# Main.net
KiCad netlist of a schematic drawn in Altium Designer
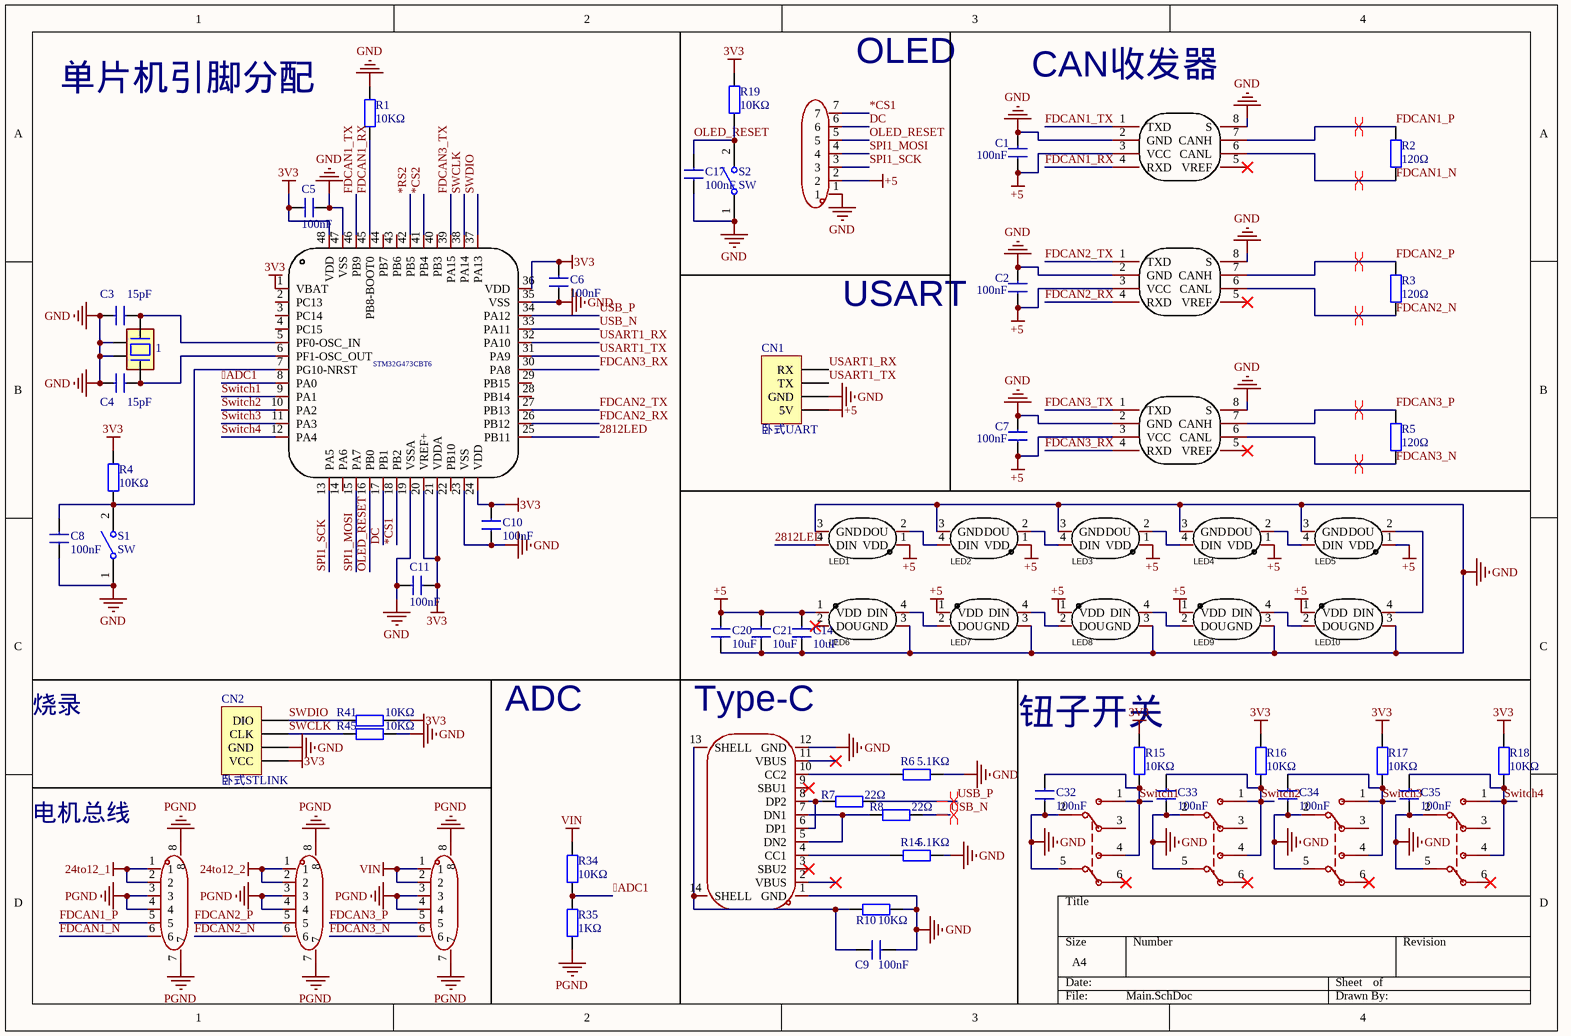
[diagram p0: Main.SchDoc]

(export (version "E")
  (design (tool "Eeschema 10.0.6"))
  (components
    (comp (ref "1")
      (value "3225贴片晶振")
      (footprint "OSC-3225-4P")
      (libsource (lib "Integrated_Library1") (part "3225贴片晶振"))
    )
    (comp (ref "C1")
      (value "100nF")
      (footprint "c0402")
      (description "贴片电容0402")
      (libsource (lib "Integrated_Library1") (part "0402贴片电容"))
    )
    (comp (ref "C2")
      (value "100nF")
      (footprint "c0402")
      (description "贴片电容0402")
      (libsource (lib "Integrated_Library1") (part "0402贴片电容"))
    )
    (comp (ref "C3")
      (value "15pF")
      (footprint "c0402")
      (description "贴片电容0402")
      (libsource (lib "Integrated_Library1") (part "0402贴片电容"))
    )
    (comp (ref "C4")
      (value "15pF")
      (footprint "c0402")
      (description "贴片电容0402")
      (libsource (lib "Integrated_Library1") (part "0402贴片电容"))
    )
    (comp (ref "C5")
      (value "100nF")
      (footprint "c0402")
      (description "贴片电容0402")
      (libsource (lib "Integrated_Library1") (part "0402贴片电容"))
    )
    (comp (ref "C6")
      (value "100nF")
      (footprint "c0402")
      (description "贴片电容0402")
      (libsource (lib "Integrated_Library1") (part "0402贴片电容"))
    )
    (comp (ref "C7")
      (value "100nF")
      (footprint "c0402")
      (description "贴片电容0402")
      (libsource (lib "Integrated_Library1") (part "0402贴片电容"))
    )
    (comp (ref "C8")
      (value "100nF")
      (footprint "c0402")
      (description "贴片电容0402")
      (libsource (lib "Integrated_Library1") (part "0402贴片电容"))
    )
    (comp (ref "C9")
      (value "100nF")
      (footprint "c0402")
      (description "贴片电容0402")
      (libsource (lib "Integrated_Library1") (part "0402贴片电容"))
    )
    (comp (ref "C10")
      (value "100nF")
      (footprint "c0402")
      (description "贴片电容0402")
      (libsource (lib "Integrated_Library1") (part "0402贴片电容"))
    )
    (comp (ref "C11")
      (value "100nF")
      (footprint "c0402")
      (description "贴片电容0402")
      (libsource (lib "Integrated_Library1") (part "0402贴片电容"))
    )
    (comp (ref "C14")
      (value "10uF")
      (footprint "1210")
      (description "1210贴片电容")
      (libsource (lib "Integrated_Library1") (part "1210贴片电容"))
    )
    (comp (ref "C17")
      (value "100nF")
      (footprint "c0402")
      (description "贴片电容0402")
      (libsource (lib "Integrated_Library1") (part "0402贴片电容"))
    )
    (comp (ref "C20")
      (value "10uF")
      (footprint "1210")
      (description "1210贴片电容")
      (libsource (lib "Integrated_Library1") (part "1210贴片电容"))
    )
    (comp (ref "C21")
      (value "10uF")
      (footprint "1210")
      (description "1210贴片电容")
      (libsource (lib "Integrated_Library1") (part "1210贴片电容"))
    )
    (comp (ref "C32")
      (value "100nF")
      (footprint "c0402")
      (description "贴片电容0402")
      (libsource (lib "Integrated_Library1") (part "0402贴片电容"))
    )
    (comp (ref "C33")
      (value "100nF")
      (footprint "c0402")
      (description "贴片电容0402")
      (libsource (lib "Integrated_Library1") (part "0402贴片电容"))
    )
    (comp (ref "C34")
      (value "100nF")
      (footprint "c0402")
      (description "贴片电容0402")
      (libsource (lib "Integrated_Library1") (part "0402贴片电容"))
    )
    (comp (ref "C35")
      (value "100nF")
      (footprint "c0402")
      (description "贴片电容0402")
      (libsource (lib "Integrated_Library1") (part "0402贴片电容"))
    )
    (comp (ref "CN1")
      (value "卧式UART")
      (footprint "CONN-SMD_4P-P1.25_GH1.25-4P")
      (libsource (lib "Integrated_Library1") (part "卧式UART"))
    )
    (comp (ref "CN2")
      (value "卧式STLINK")
      (footprint "CONN-SMD_4P-P1.25_GH1.25-4P")
      (libsource (lib "Integrated_Library1") (part "卧式STLINK"))
    )
    (comp (ref "H1")
      (value "PM254V-11-07-H85")
      (footprint "HDR-TH_7P-P2.54-V-F")
      (fields (field (name "MANUFACTURER") "XFCN(兴飞)"))
      (libsource (lib "Schlib1") (part "PM254V-11-07-H85"))
    )
    (comp (ref "LED1")
      (value "XL-5050RGBC-WS2812B")
      (footprint "LED-SMD_4P-L5.0-W5.0-BL_XL-5050RGBC")
      (description "WS2812B彩灯珠")
      (fields (field (name "MANUFACTURER") "XINGLIGHT(成兴光)"))
      (libsource (lib "RoBoMaster_AllComponent") (part "WS2812B彩灯珠"))
    )
    (comp (ref "LED2")
      (value "XL-5050RGBC-WS2812B")
      (footprint "LED-SMD_4P-L5.0-W5.0-BL_XL-5050RGBC")
      (description "WS2812B彩灯珠")
      (fields (field (name "MANUFACTURER") "XINGLIGHT(成兴光)"))
      (libsource (lib "RoBoMaster_AllComponent") (part "WS2812B彩灯珠"))
    )
    (comp (ref "LED3")
      (value "XL-5050RGBC-WS2812B")
      (footprint "LED-SMD_4P-L5.0-W5.0-BL_XL-5050RGBC")
      (description "WS2812B彩灯珠")
      (fields (field (name "MANUFACTURER") "XINGLIGHT(成兴光)"))
      (libsource (lib "RoBoMaster_AllComponent") (part "WS2812B彩灯珠"))
    )
    (comp (ref "LED4")
      (value "XL-5050RGBC-WS2812B")
      (footprint "LED-SMD_4P-L5.0-W5.0-BL_XL-5050RGBC")
      (description "WS2812B彩灯珠")
      (fields (field (name "MANUFACTURER") "XINGLIGHT(成兴光)"))
      (libsource (lib "RoBoMaster_AllComponent") (part "WS2812B彩灯珠"))
    )
    (comp (ref "LED5")
      (value "XL-5050RGBC-WS2812B")
      (footprint "LED-SMD_4P-L5.0-W5.0-BL_XL-5050RGBC")
      (description "WS2812B彩灯珠")
      (fields (field (name "MANUFACTURER") "XINGLIGHT(成兴光)"))
      (libsource (lib "RoBoMaster_AllComponent") (part "WS2812B彩灯珠"))
    )
    (comp (ref "LED6")
      (value "XL-5050RGBC-WS2812B")
      (footprint "LED-SMD_4P-L5.0-W5.0-BL_XL-5050RGBC")
      (description "WS2812B彩灯珠")
      (fields (field (name "MANUFACTURER") "XINGLIGHT(成兴光)"))
      (libsource (lib "RoBoMaster_AllComponent") (part "WS2812B彩灯珠"))
    )
    (comp (ref "LED7")
      (value "XL-5050RGBC-WS2812B")
      (footprint "LED-SMD_4P-L5.0-W5.0-BL_XL-5050RGBC")
      (description "WS2812B彩灯珠")
      (fields (field (name "MANUFACTURER") "XINGLIGHT(成兴光)"))
      (libsource (lib "RoBoMaster_AllComponent") (part "WS2812B彩灯珠"))
    )
    (comp (ref "LED8")
      (value "XL-5050RGBC-WS2812B")
      (footprint "LED-SMD_4P-L5.0-W5.0-BL_XL-5050RGBC")
      (description "WS2812B彩灯珠")
      (fields (field (name "MANUFACTURER") "XINGLIGHT(成兴光)"))
      (libsource (lib "RoBoMaster_AllComponent") (part "WS2812B彩灯珠"))
    )
    (comp (ref "LED9")
      (value "XL-5050RGBC-WS2812B")
      (footprint "LED-SMD_4P-L5.0-W5.0-BL_XL-5050RGBC")
      (description "WS2812B彩灯珠")
      (fields (field (name "MANUFACTURER") "XINGLIGHT(成兴光)"))
      (libsource (lib "RoBoMaster_AllComponent") (part "WS2812B彩灯珠"))
    )
    (comp (ref "LED10")
      (value "XL-5050RGBC-WS2812B")
      (footprint "LED-SMD_4P-L5.0-W5.0-BL_XL-5050RGBC")
      (description "WS2812B彩灯珠")
      (fields (field (name "MANUFACTURER") "XINGLIGHT(成兴光)"))
      (libsource (lib "RoBoMaster_AllComponent") (part "WS2812B彩灯珠"))
    )
    (comp (ref "R1")
      (value "10KΩ")
      (footprint "R0402")
      (description "0402贴片电阻")
      (libsource (lib "") (part "0402贴片电阻_2"))
    )
    (comp (ref "R2")
      (value "120Ω")
      (footprint "R0402")
      (description "0402贴片电阻")
      (libsource (lib "Integrated_Library1") (part "0402贴片电阻"))
    )
    (comp (ref "R3")
      (value "120Ω")
      (footprint "R0402")
      (description "0402贴片电阻")
      (libsource (lib "Integrated_Library1") (part "0402贴片电阻"))
    )
    (comp (ref "R4")
      (value "10KΩ")
      (footprint "R0402")
      (description "0402贴片电阻")
      (libsource (lib "Integrated_Library1") (part "0402贴片电阻"))
    )
    (comp (ref "R5")
      (value "120Ω")
      (footprint "R0402")
      (description "0402贴片电阻")
      (libsource (lib "Integrated_Library1") (part "0402贴片电阻"))
    )
    (comp (ref "R6")
      (value "5.1KΩ")
      (footprint "R0402")
      (description "0402贴片电阻")
      (libsource (lib "") (part "0402贴片电阻_1"))
    )
    (comp (ref "R7")
      (value "22Ω")
      (footprint "R0402")
      (description "0402贴片电阻")
      (libsource (lib "") (part "0402贴片电阻_1"))
    )
    (comp (ref "R8")
      (value "22Ω")
      (footprint "R0402")
      (description "0402贴片电阻")
      (libsource (lib "") (part "0402贴片电阻_1"))
    )
    (comp (ref "R10")
      (value "10KΩ")
      (footprint "R0402")
      (description "0402贴片电阻")
      (libsource (lib "") (part "0402贴片电阻_1"))
    )
    (comp (ref "R14")
      (value "5.1KΩ")
      (footprint "R0402")
      (description "0402贴片电阻")
      (libsource (lib "") (part "0402贴片电阻_1"))
    )
    (comp (ref "R15")
      (value "10KΩ")
      (footprint "R0402")
      (description "0402贴片电阻")
      (libsource (lib "Integrated_Library1") (part "0402贴片电阻"))
    )
    (comp (ref "R16")
      (value "10KΩ")
      (footprint "R0402")
      (description "0402贴片电阻")
      (libsource (lib "Integrated_Library1") (part "0402贴片电阻"))
    )
    (comp (ref "R17")
      (value "10KΩ")
      (footprint "R0402")
      (description "0402贴片电阻")
      (libsource (lib "Integrated_Library1") (part "0402贴片电阻"))
    )
    (comp (ref "R18")
      (value "10KΩ")
      (footprint "R0402")
      (description "0402贴片电阻")
      (libsource (lib "Integrated_Library1") (part "0402贴片电阻"))
    )
    (comp (ref "R19")
      (value "10KΩ")
      (footprint "R0402")
      (description "0402贴片电阻")
      (libsource (lib "Integrated_Library1") (part "0402贴片电阻"))
    )
    (comp (ref "R34")
      (value "10KΩ")
      (footprint "R0402")
      (description "0402贴片电阻")
      (libsource (lib "") (part "0402贴片电阻_3"))
    )
    (comp (ref "R35")
      (value "1KΩ")
      (footprint "R0402")
      (description "0402贴片电阻")
      (libsource (lib "") (part "0402贴片电阻_3"))
    )
    (comp (ref "R41")
      (value "10KΩ")
      (footprint "R0402")
      (description "0402贴片电阻")
      (libsource (lib "") (part "0402贴片电阻_1"))
    )
    (comp (ref "R45")
      (value "10KΩ")
      (footprint "R0402")
      (description "0402贴片电阻")
      (libsource (lib "") (part "0402贴片电阻_1"))
    )
    (comp (ref "S1")
      (value "SW")
      (footprint "KEY_SMD")
      (description "开关")
      (libsource (lib "Integrated_Library1") (part "SW"))
    )
    (comp (ref "S2")
      (value "SW")
      (footprint "KEY_SMD")
      (description "开关")
      (libsource (lib "Integrated_Library1") (part "SW"))
    )
    (comp (ref "U1")
      (value "ZX-ZH1.5-6PWT")
      (footprint "CONN-SMD_6P-P1.50_ZX-ZH1.5-6PWT")
      (fields (field (name "MANUFACTURER") "Megastar(兆星)"))
      (libsource (lib "Schlib1") (part "ZX-ZH1.5-6PWT"))
    )
    (comp (ref "U2")
      (value "SN65HVD1050DR")
      (footprint "SOIC-8_L4.9-W3.9-P1.27-LS6.0-BL")
      (description "CAN芯片")
      (fields (field (name "MANUFACTURER") "TI(德州仪器)"))
      (libsource (lib "Integrated_Library1") (part "SN65HVD1050DR"))
    )
    (comp (ref "U3")
      (value "ZX-ZH1.5-6PWT")
      (footprint "CONN-SMD_6P-P1.50_ZX-ZH1.5-6PWT")
      (fields (field (name "MANUFACTURER") "Megastar(兆星)"))
      (libsource (lib "Schlib1") (part "ZX-ZH1.5-6PWT"))
    )
    (comp (ref "U4")
      (value "STM32G474CET6")
      (footprint "LQFP-48")
      (fields (field (name "MANUFACTURER") "ST(意法半导体)") (field (name "MANUFACTURER PART") "STM32G473CBT6"))
      (libsource (lib "Integrated_Library1") (part "STM32G474CET6"))
    )
    (comp (ref "U5")
      (value "SN65HVD1050DR")
      (footprint "SOIC-8_L4.9-W3.9-P1.27-LS6.0-BL")
      (description "CAN芯片")
      (fields (field (name "MANUFACTURER") "TI(德州仪器)"))
      (libsource (lib "Integrated_Library1") (part "SN65HVD1050DR"))
    )
    (comp (ref "U6")
      (value "ZX-ZH1.5-6PWT")
      (footprint "CONN-SMD_6P-P1.50_ZX-ZH1.5-6PWT")
      (fields (field (name "MANUFACTURER") "Megastar(兆星)"))
      (libsource (lib "Schlib1") (part "ZX-ZH1.5-6PWT"))
    )
    (comp (ref "U8")
      (value "SN65HVD1050DR")
      (footprint "SOIC-8_L4.9-W3.9-P1.27-LS6.0-BL")
      (description "CAN芯片")
      (fields (field (name "MANUFACTURER") "TI(德州仪器)"))
      (libsource (lib "Integrated_Library1") (part "SN65HVD1050DR"))
    )
    (comp (ref "U9")
      (value "7208P1YZQI")
      (footprint "SW-TH_6P-L12.7-W11.4-P4.70-LS4.8")
      (fields (field (name "MANUFACTURER") "C&K"))
      (libsource (lib "Schlib1") (part "7208P1YZQI"))
    )
    (comp (ref "U10")
      (value "7208P1YZQI")
      (footprint "SW-TH_6P-L12.7-W11.4-P4.70-LS4.8")
      (fields (field (name "MANUFACTURER") "C&K"))
      (libsource (lib "Schlib1") (part "7208P1YZQI"))
    )
    (comp (ref "U11")
      (value "7208P1YZQI")
      (footprint "SW-TH_6P-L12.7-W11.4-P4.70-LS4.8")
      (fields (field (name "MANUFACTURER") "C&K"))
      (libsource (lib "Schlib1") (part "7208P1YZQI"))
    )
    (comp (ref "U12")
      (value "7208P1YZQI")
      (footprint "SW-TH_6P-L12.7-W11.4-P4.70-LS4.8")
      (fields (field (name "MANUFACTURER") "C&K"))
      (libsource (lib "Schlib1") (part "7208P1YZQI"))
    )
    (comp (ref "USB1")
      (value "TYPE-C 16PIN 2MD(073)")
      (footprint "USB-C-SMD_TYPE-C-6PIN-2MD-073")
      (fields (field (name "MANUFACTURER") "SHOU HAN(首韩)"))
      (libsource (lib "Schlib1") (part "TYPE-C 16PIN 2MD(073)"))
    )
  )
  (nets
    (net (code "1") (name "+5") (class "Default")
      (node (ref "C1") (pin "1") (pinfunction "1_1") (pintype "passive"))
      (node (ref "C14") (pin "2") (pinfunction "2_2") (pintype "passive"))
      (node (ref "C2") (pin "1") (pinfunction "1_1") (pintype "passive"))
      (node (ref "C20") (pin "2") (pinfunction "2_2") (pintype "passive"))
      (node (ref "C21") (pin "2") (pinfunction "2_2") (pintype "passive"))
      (node (ref "C7") (pin "1") (pinfunction "1_1") (pintype "passive"))
      (node (ref "CN1") (pin "1") (pinfunction "5V_1") (pintype "passive"))
      (node (ref "H1") (pin "2") (pinfunction "2_2") (pintype "passive"))
      (node (ref "LED1") (pin "1") (pinfunction "VDD_1") (pintype "passive"))
      (node (ref "LED10") (pin "1") (pinfunction "VDD_1") (pintype "passive"))
      (node (ref "LED2") (pin "1") (pinfunction "VDD_1") (pintype "passive"))
      (node (ref "LED3") (pin "1") (pinfunction "VDD_1") (pintype "passive"))
      (node (ref "LED4") (pin "1") (pinfunction "VDD_1") (pintype "passive"))
      (node (ref "LED5") (pin "1") (pinfunction "VDD_1") (pintype "passive"))
      (node (ref "LED6") (pin "1") (pinfunction "VDD_1") (pintype "passive"))
      (node (ref "LED7") (pin "1") (pinfunction "VDD_1") (pintype "passive"))
      (node (ref "LED8") (pin "1") (pinfunction "VDD_1") (pintype "passive"))
      (node (ref "LED9") (pin "1") (pinfunction "VDD_1") (pintype "passive"))
      (node (ref "U2") (pin "3") (pinfunction "VCC_3") (pintype "passive"))
      (node (ref "U5") (pin "3") (pinfunction "VCC_3") (pintype "passive"))
      (node (ref "U8") (pin "3") (pinfunction "VCC_3") (pintype "passive"))
    )
    (net (code "2") (name "/ADC1") (class "Default")
      (node (ref "R34") (pin "1") (pinfunction "1_1") (pintype "passive"))
      (node (ref "R35") (pin "2") (pinfunction "2_2") (pintype "passive"))
      (node (ref "U4") (pin "8") (pinfunction "PA0_8") (pintype "passive"))
    )
    (net (code "3") (name "/*CS1") (class "Default")
      (node (ref "H1") (pin "7") (pinfunction "7_7") (pintype "passive"))
      (node (ref "U4") (pin "18") (pinfunction "PB2_18") (pintype "passive"))
    )
    (net (code "4") (name "/*CS2") (class "Default")
      (node (ref "U4") (pin "41") (pinfunction "PB4_41") (pintype "passive"))
    )
    (net (code "5") (name "/*RS2") (class "Default")
      (node (ref "U4") (pin "42") (pinfunction "PB5_42") (pintype "passive"))
    )
    (net (code "6") (name "/2812LED") (class "Default")
      (node (ref "LED1") (pin "4") (pinfunction "DIN_4") (pintype "passive"))
      (node (ref "U4") (pin "25") (pinfunction "PB11_25") (pintype "passive"))
    )
    (net (code "7") (name "/DC") (class "Default")
      (node (ref "H1") (pin "6") (pinfunction "6_6") (pintype "passive"))
      (node (ref "U4") (pin "17") (pinfunction "PB1_17") (pintype "passive"))
    )
    (net (code "8") (name "/FDCAN1_N") (class "Default")
      (node (ref "R2") (pin "1") (pinfunction "1_1") (pintype "passive"))
      (node (ref "U1") (pin "6") (pinfunction "6_6") (pintype "passive"))
      (node (ref "U2") (pin "6") (pinfunction "CANL_6") (pintype "passive"))
    )
    (net (code "9") (name "/FDCAN1_P") (class "Default")
      (node (ref "R2") (pin "2") (pinfunction "2_2") (pintype "passive"))
      (node (ref "U1") (pin "5") (pinfunction "5_5") (pintype "passive"))
      (node (ref "U2") (pin "7") (pinfunction "CANH_7") (pintype "passive"))
    )
    (net (code "10") (name "/FDCAN1_RX") (class "Default")
      (node (ref "R1") (pin "2") (pinfunction "2_2") (pintype "passive"))
      (node (ref "U2") (pin "4") (pinfunction "RXD_4") (pintype "passive"))
      (node (ref "U4") (pin "45") (pinfunction "PB8-BOOT0_45") (pintype "passive"))
    )
    (net (code "11") (name "/FDCAN1_TX") (class "Default")
      (node (ref "U2") (pin "1") (pinfunction "TXD_1") (pintype "passive"))
      (node (ref "U4") (pin "46") (pinfunction "PB9_46") (pintype "passive"))
    )
    (net (code "12") (name "/FDCAN2_N") (class "Default")
      (node (ref "R3") (pin "1") (pinfunction "1_1") (pintype "passive"))
      (node (ref "U3") (pin "6") (pinfunction "6_6") (pintype "passive"))
      (node (ref "U5") (pin "6") (pinfunction "CANL_6") (pintype "passive"))
    )
    (net (code "13") (name "/FDCAN2_P") (class "Default")
      (node (ref "R3") (pin "2") (pinfunction "2_2") (pintype "passive"))
      (node (ref "U3") (pin "5") (pinfunction "5_5") (pintype "passive"))
      (node (ref "U5") (pin "7") (pinfunction "CANH_7") (pintype "passive"))
    )
    (net (code "14") (name "/FDCAN2_RX") (class "Default")
      (node (ref "U4") (pin "26") (pinfunction "PB12_26") (pintype "passive"))
      (node (ref "U5") (pin "4") (pinfunction "RXD_4") (pintype "passive"))
    )
    (net (code "15") (name "/FDCAN2_TX") (class "Default")
      (node (ref "U4") (pin "27") (pinfunction "PB13_27") (pintype "passive"))
      (node (ref "U5") (pin "1") (pinfunction "TXD_1") (pintype "passive"))
    )
    (net (code "16") (name "/FDCAN3_N") (class "Default")
      (node (ref "R5") (pin "1") (pinfunction "1_1") (pintype "passive"))
      (node (ref "U6") (pin "6") (pinfunction "6_6") (pintype "passive"))
      (node (ref "U8") (pin "6") (pinfunction "CANL_6") (pintype "passive"))
    )
    (net (code "17") (name "/FDCAN3_P") (class "Default")
      (node (ref "R5") (pin "2") (pinfunction "2_2") (pintype "passive"))
      (node (ref "U6") (pin "5") (pinfunction "5_5") (pintype "passive"))
      (node (ref "U8") (pin "7") (pinfunction "CANH_7") (pintype "passive"))
    )
    (net (code "18") (name "/FDCAN3_RX") (class "Default")
      (node (ref "U4") (pin "30") (pinfunction "PA8_30") (pintype "passive"))
      (node (ref "U8") (pin "4") (pinfunction "RXD_4") (pintype "passive"))
    )
    (net (code "19") (name "/FDCAN3_TX") (class "Default")
      (node (ref "U4") (pin "39") (pinfunction "PA15_39") (pintype "passive"))
      (node (ref "U8") (pin "1") (pinfunction "TXD_1") (pintype "passive"))
    )
    (net (code "20") (name "/OLED_RESET") (class "Default")
      (node (ref "C17") (pin "2") (pinfunction "2_2") (pintype "passive"))
      (node (ref "H1") (pin "5") (pinfunction "5_5") (pintype "passive"))
      (node (ref "R19") (pin "1") (pinfunction "1_1") (pintype "passive"))
      (node (ref "S2") (pin "2") (pinfunction "NO_2") (pintype "passive"))
      (node (ref "U4") (pin "16") (pinfunction "PB0_16") (pintype "passive"))
    )
    (net (code "21") (name "/SPI1_MOSI") (class "Default")
      (node (ref "H1") (pin "4") (pinfunction "4_4") (pintype "passive"))
      (node (ref "U4") (pin "15") (pinfunction "PA7_15") (pintype "passive"))
    )
    (net (code "22") (name "/SPI1_SCK") (class "Default")
      (node (ref "H1") (pin "3") (pinfunction "3_3") (pintype "passive"))
      (node (ref "U4") (pin "13") (pinfunction "PA5_13") (pintype "passive"))
    )
    (net (code "23") (name "/SWCLK") (class "Default")
      (node (ref "CN2") (pin "3") (pinfunction "CLK_3") (pintype "passive"))
      (node (ref "R45") (pin "1") (pinfunction "1_1") (pintype "passive"))
      (node (ref "U4") (pin "38") (pinfunction "PA14_38") (pintype "passive"))
    )
    (net (code "24") (name "/SWDIO") (class "Default")
      (node (ref "CN2") (pin "4") (pinfunction "DIO_4") (pintype "passive"))
      (node (ref "R41") (pin "1") (pinfunction "1_1") (pintype "passive"))
      (node (ref "U4") (pin "37") (pinfunction "PA13_37") (pintype "passive"))
    )
    (net (code "25") (name "/Switch1") (class "Default")
      (node (ref "C32") (pin "2") (pinfunction "2_2") (pintype "passive"))
      (node (ref "R15") (pin "1") (pinfunction "1_1") (pintype "passive"))
      (node (ref "U4") (pin "9") (pinfunction "PA1_9") (pintype "passive"))
      (node (ref "U9") (pin "1") (pinfunction "1_1") (pintype "passive"))
      (node (ref "U9") (pin "4") (pinfunction "4_4") (pintype "passive"))
    )
    (net (code "26") (name "/Switch2") (class "Default")
      (node (ref "C33") (pin "2") (pinfunction "2_2") (pintype "passive"))
      (node (ref "R16") (pin "1") (pinfunction "1_1") (pintype "passive"))
      (node (ref "U10") (pin "1") (pinfunction "1_1") (pintype "passive"))
      (node (ref "U10") (pin "4") (pinfunction "4_4") (pintype "passive"))
      (node (ref "U4") (pin "10") (pinfunction "PA2_10") (pintype "passive"))
    )
    (net (code "27") (name "/Switch3") (class "Default")
      (node (ref "C34") (pin "2") (pinfunction "2_2") (pintype "passive"))
      (node (ref "R17") (pin "1") (pinfunction "1_1") (pintype "passive"))
      (node (ref "U11") (pin "1") (pinfunction "1_1") (pintype "passive"))
      (node (ref "U11") (pin "4") (pinfunction "4_4") (pintype "passive"))
      (node (ref "U4") (pin "11") (pinfunction "PA3_11") (pintype "passive"))
    )
    (net (code "28") (name "/Switch4") (class "Default")
      (node (ref "C35") (pin "2") (pinfunction "2_2") (pintype "passive"))
      (node (ref "R18") (pin "1") (pinfunction "1_1") (pintype "passive"))
      (node (ref "U12") (pin "1") (pinfunction "1_1") (pintype "passive"))
      (node (ref "U12") (pin "4") (pinfunction "4_4") (pintype "passive"))
      (node (ref "U4") (pin "12") (pinfunction "PA4_12") (pintype "passive"))
    )
    (net (code "29") (name "/USART1_RX") (class "Default")
      (node (ref "CN1") (pin "4") (pinfunction "RX_4") (pintype "passive"))
      (node (ref "U4") (pin "32") (pinfunction "PA10_32") (pintype "passive"))
    )
    (net (code "30") (name "/USART1_TX") (class "Default")
      (node (ref "CN1") (pin "3") (pinfunction "TX_3") (pintype "passive"))
      (node (ref "U4") (pin "31") (pinfunction "PA9_31") (pintype "passive"))
    )
    (net (code "31") (name "/USB_N") (class "Default")
      (node (ref "R8") (pin "2") (pinfunction "2_2") (pintype "passive"))
      (node (ref "U4") (pin "33") (pinfunction "PA11_33") (pintype "passive"))
    )
    (net (code "32") (name "/USB_P") (class "Default")
      (node (ref "R7") (pin "2") (pinfunction "2_2") (pintype "passive"))
      (node (ref "U4") (pin "34") (pinfunction "PA12_34") (pintype "passive"))
    )
    (net (code "33") (name "3V3") (class "Default")
      (node (ref "C10") (pin "2") (pinfunction "2_2") (pintype "passive"))
      (node (ref "C11") (pin "1") (pinfunction "1_1") (pintype "passive"))
      (node (ref "C5") (pin "2") (pinfunction "2_2") (pintype "passive"))
      (node (ref "C6") (pin "2") (pinfunction "2_2") (pintype "passive"))
      (node (ref "CN2") (pin "1") (pinfunction "VCC_1") (pintype "passive"))
      (node (ref "R15") (pin "2") (pinfunction "2_2") (pintype "passive"))
      (node (ref "R16") (pin "2") (pinfunction "2_2") (pintype "passive"))
      (node (ref "R17") (pin "2") (pinfunction "2_2") (pintype "passive"))
      (node (ref "R18") (pin "2") (pinfunction "2_2") (pintype "passive"))
      (node (ref "R19") (pin "2") (pinfunction "2_2") (pintype "passive"))
      (node (ref "R4") (pin "2") (pinfunction "2_2") (pintype "passive"))
      (node (ref "R41") (pin "2") (pinfunction "2_2") (pintype "passive"))
      (node (ref "U4") (pin "1") (pinfunction "VBAT_1") (pintype "passive"))
      (node (ref "U4") (pin "20") (pinfunction "VREF+_20") (pintype "passive"))
      (node (ref "U4") (pin "21") (pinfunction "VDDA_21") (pintype "passive"))
      (node (ref "U4") (pin "24") (pinfunction "VDD_24") (pintype "passive"))
      (node (ref "U4") (pin "36") (pinfunction "VDD_36") (pintype "passive"))
      (node (ref "U4") (pin "48") (pinfunction "VDD_48") (pintype "passive"))
    )
    (net (code "34") (name "24to12_1") (class "Default")
      (node (ref "U1") (pin "1") (pinfunction "1_1") (pintype "passive"))
      (node (ref "U1") (pin "2") (pinfunction "2_2") (pintype "passive"))
    )
    (net (code "35") (name "24to12_2") (class "Default")
      (node (ref "U3") (pin "1") (pinfunction "1_1") (pintype "passive"))
      (node (ref "U3") (pin "2") (pinfunction "2_2") (pintype "passive"))
    )
    (net (code "36") (name "GND") (class "Default")
      (node (ref "1") (pin "2") (pinfunction "2_2") (pintype "passive"))
      (node (ref "1") (pin "4") (pinfunction "4_4") (pintype "passive"))
      (node (ref "C1") (pin "2") (pinfunction "2_2") (pintype "passive"))
      (node (ref "C10") (pin "1") (pinfunction "1_1") (pintype "passive"))
      (node (ref "C11") (pin "2") (pinfunction "2_2") (pintype "passive"))
      (node (ref "C14") (pin "1") (pinfunction "1_1") (pintype "passive"))
      (node (ref "C17") (pin "1") (pinfunction "1_1") (pintype "passive"))
      (node (ref "C2") (pin "2") (pinfunction "2_2") (pintype "passive"))
      (node (ref "C20") (pin "1") (pinfunction "1_1") (pintype "passive"))
      (node (ref "C21") (pin "1") (pinfunction "1_1") (pintype "passive"))
      (node (ref "C3") (pin "1") (pinfunction "1_1") (pintype "passive"))
      (node (ref "C32") (pin "1") (pinfunction "1_1") (pintype "passive"))
      (node (ref "C33") (pin "1") (pinfunction "1_1") (pintype "passive"))
      (node (ref "C34") (pin "1") (pinfunction "1_1") (pintype "passive"))
      (node (ref "C35") (pin "1") (pinfunction "1_1") (pintype "passive"))
      (node (ref "C4") (pin "1") (pinfunction "1_1") (pintype "passive"))
      (node (ref "C5") (pin "1") (pinfunction "1_1") (pintype "passive"))
      (node (ref "C6") (pin "1") (pinfunction "1_1") (pintype "passive"))
      (node (ref "C7") (pin "2") (pinfunction "2_2") (pintype "passive"))
      (node (ref "C8") (pin "1") (pinfunction "1_1") (pintype "passive"))
      (node (ref "C9") (pin "2") (pinfunction "2_2") (pintype "passive"))
      (node (ref "CN1") (pin "2") (pinfunction "GND_2") (pintype "passive"))
      (node (ref "CN2") (pin "2") (pinfunction "GND_2") (pintype "passive"))
      (node (ref "H1") (pin "1") (pinfunction "1_1") (pintype "passive"))
      (node (ref "LED1") (pin "3") (pinfunction "GND_3") (pintype "passive"))
      (node (ref "LED10") (pin "3") (pinfunction "GND_3") (pintype "passive"))
      (node (ref "LED2") (pin "3") (pinfunction "GND_3") (pintype "passive"))
      (node (ref "LED3") (pin "3") (pinfunction "GND_3") (pintype "passive"))
      (node (ref "LED4") (pin "3") (pinfunction "GND_3") (pintype "passive"))
      (node (ref "LED5") (pin "3") (pinfunction "GND_3") (pintype "passive"))
      (node (ref "LED6") (pin "3") (pinfunction "GND_3") (pintype "passive"))
      (node (ref "LED7") (pin "3") (pinfunction "GND_3") (pintype "passive"))
      (node (ref "LED8") (pin "3") (pinfunction "GND_3") (pintype "passive"))
      (node (ref "LED9") (pin "3") (pinfunction "GND_3") (pintype "passive"))
      (node (ref "R1") (pin "1") (pinfunction "1_1") (pintype "passive"))
      (node (ref "R10") (pin "2") (pinfunction "2_2") (pintype "passive"))
      (node (ref "R14") (pin "2") (pinfunction "2_2") (pintype "passive"))
      (node (ref "R45") (pin "2") (pinfunction "2_2") (pintype "passive"))
      (node (ref "R6") (pin "2") (pinfunction "2_2") (pintype "passive"))
      (node (ref "S1") (pin "1") (pinfunction "COMMON_1") (pintype "passive"))
      (node (ref "S2") (pin "1") (pinfunction "COMMON_1") (pintype "passive"))
      (node (ref "U10") (pin "2") (pinfunction "2_2") (pintype "passive"))
      (node (ref "U10") (pin "5") (pinfunction "5_5") (pintype "passive"))
      (node (ref "U11") (pin "2") (pinfunction "2_2") (pintype "passive"))
      (node (ref "U11") (pin "5") (pinfunction "5_5") (pintype "passive"))
      (node (ref "U12") (pin "2") (pinfunction "2_2") (pintype "passive"))
      (node (ref "U12") (pin "5") (pinfunction "5_5") (pintype "passive"))
      (node (ref "U2") (pin "2") (pinfunction "GND_2") (pintype "passive"))
      (node (ref "U2") (pin "8") (pinfunction "S_8") (pintype "passive"))
      (node (ref "U4") (pin "19") (pinfunction "VSSA_19") (pintype "passive"))
      (node (ref "U4") (pin "23") (pinfunction "VSS_23") (pintype "passive"))
      (node (ref "U4") (pin "35") (pinfunction "VSS_35") (pintype "passive"))
      (node (ref "U4") (pin "47") (pinfunction "VSS_47") (pintype "passive"))
      (node (ref "U5") (pin "2") (pinfunction "GND_2") (pintype "passive"))
      (node (ref "U5") (pin "8") (pinfunction "S_8") (pintype "passive"))
      (node (ref "U8") (pin "2") (pinfunction "GND_2") (pintype "passive"))
      (node (ref "U8") (pin "8") (pinfunction "S_8") (pintype "passive"))
      (node (ref "U9") (pin "2") (pinfunction "2_2") (pintype "passive"))
      (node (ref "U9") (pin "5") (pinfunction "5_5") (pintype "passive"))
      (node (ref "USB1") (pin "1") (pinfunction "GND_1") (pintype "passive"))
      (node (ref "USB1") (pin "12") (pinfunction "GND_12") (pintype "passive"))
    )
    (net (code "37") (name "Net-(C9-Pad1)") (class "Default")
      (node (ref "C9") (pin "1") (pinfunction "1_1") (pintype "passive"))
      (node (ref "R10") (pin "1") (pinfunction "1_1") (pintype "passive"))
      (node (ref "USB1") (pin "13") (pinfunction "SHELL_13") (pintype "passive"))
      (node (ref "USB1") (pin "14") (pinfunction "SHELL_14") (pintype "passive"))
    )
    (net (code "38") (name "Net-(LED1-DOU)") (class "Default")
      (node (ref "LED1") (pin "2") (pinfunction "DOU_2") (pintype "passive"))
      (node (ref "LED2") (pin "4") (pinfunction "DIN_4") (pintype "passive"))
    )
    (net (code "39") (name "Net-(LED2-DOU)") (class "Default")
      (node (ref "LED2") (pin "2") (pinfunction "DOU_2") (pintype "passive"))
      (node (ref "LED3") (pin "4") (pinfunction "DIN_4") (pintype "passive"))
    )
    (net (code "40") (name "Net-(LED3-DOU)") (class "Default")
      (node (ref "LED3") (pin "2") (pinfunction "DOU_2") (pintype "passive"))
      (node (ref "LED4") (pin "4") (pinfunction "DIN_4") (pintype "passive"))
    )
    (net (code "41") (name "Net-(LED4-DOU)") (class "Default")
      (node (ref "LED4") (pin "2") (pinfunction "DOU_2") (pintype "passive"))
      (node (ref "LED5") (pin "4") (pinfunction "DIN_4") (pintype "passive"))
    )
    (net (code "42") (name "Net-(LED6-DIN)") (class "Default")
      (node (ref "LED6") (pin "4") (pinfunction "DIN_4") (pintype "passive"))
      (node (ref "LED7") (pin "2") (pinfunction "DOU_2") (pintype "passive"))
    )
    (net (code "43") (name "Net-(LED7-DIN)") (class "Default")
      (node (ref "LED7") (pin "4") (pinfunction "DIN_4") (pintype "passive"))
      (node (ref "LED8") (pin "2") (pinfunction "DOU_2") (pintype "passive"))
    )
    (net (code "44") (name "Net-(LED8-DIN)") (class "Default")
      (node (ref "LED8") (pin "4") (pinfunction "DIN_4") (pintype "passive"))
      (node (ref "LED9") (pin "2") (pinfunction "DOU_2") (pintype "passive"))
    )
    (net (code "45") (name "Net-(LED10-DIN)") (class "Default")
      (node (ref "LED10") (pin "4") (pinfunction "DIN_4") (pintype "passive"))
      (node (ref "LED5") (pin "2") (pinfunction "DOU_2") (pintype "passive"))
    )
    (net (code "46") (name "Net-(LED10-DOU)") (class "Default")
      (node (ref "LED10") (pin "2") (pinfunction "DOU_2") (pintype "passive"))
      (node (ref "LED9") (pin "4") (pinfunction "DIN_4") (pintype "passive"))
    )
    (net (code "47") (name "Net-(S1-NO)") (class "Default")
      (node (ref "C8") (pin "2") (pinfunction "2_2") (pintype "passive"))
      (node (ref "R4") (pin "1") (pinfunction "1_1") (pintype "passive"))
      (node (ref "S1") (pin "2") (pinfunction "NO_2") (pintype "passive"))
      (node (ref "U4") (pin "7") (pinfunction "PG10-NRST_7") (pintype "passive"))
    )
    (net (code "48") (name "Net-(U4-PF0-OSC_IN)") (class "Default")
      (node (ref "1") (pin "3") (pinfunction "3_3") (pintype "passive"))
      (node (ref "C3") (pin "2") (pinfunction "2_2") (pintype "passive"))
      (node (ref "U4") (pin "5") (pinfunction "PF0-OSC_IN_5") (pintype "passive"))
    )
    (net (code "49") (name "Net-(U4-PF1-OSC_OUT)") (class "Default")
      (node (ref "1") (pin "1") (pinfunction "1_1") (pintype "passive"))
      (node (ref "C4") (pin "2") (pinfunction "2_2") (pintype "passive"))
      (node (ref "U4") (pin "6") (pinfunction "PF1-OSC_OUT_6") (pintype "passive"))
    )
    (net (code "50") (name "Net-(USB1-CC1)") (class "Default")
      (node (ref "R14") (pin "1") (pinfunction "1_1") (pintype "passive"))
      (node (ref "USB1") (pin "4") (pinfunction "CC1_4") (pintype "passive"))
    )
    (net (code "51") (name "Net-(USB1-CC2)") (class "Default")
      (node (ref "R6") (pin "1") (pinfunction "1_1") (pintype "passive"))
      (node (ref "USB1") (pin "10") (pinfunction "CC2_10") (pintype "passive"))
    )
    (net (code "52") (name "Net-(USB1-DN1)") (class "Default")
      (node (ref "R8") (pin "1") (pinfunction "1_1") (pintype "passive"))
      (node (ref "USB1") (pin "5") (pinfunction "DN2_5") (pintype "passive"))
      (node (ref "USB1") (pin "7") (pinfunction "DN1_7") (pintype "passive"))
    )
    (net (code "53") (name "Net-(USB1-DP1)") (class "Default")
      (node (ref "R7") (pin "1") (pinfunction "1_1") (pintype "passive"))
      (node (ref "USB1") (pin "6") (pinfunction "DP1_6") (pintype "passive"))
      (node (ref "USB1") (pin "8") (pinfunction "DP2_8") (pintype "passive"))
    )
    (net (code "54") (name "PGND") (class "Default")
      (node (ref "R35") (pin "1") (pinfunction "1_1") (pintype "passive"))
      (node (ref "U1") (pin "3") (pinfunction "3_3") (pintype "passive"))
      (node (ref "U1") (pin "4") (pinfunction "4_4") (pintype "passive"))
      (node (ref "U1") (pin "7") (pinfunction "7_7") (pintype "passive"))
      (node (ref "U1") (pin "8") (pinfunction "8_8") (pintype "passive"))
      (node (ref "U3") (pin "3") (pinfunction "3_3") (pintype "passive"))
      (node (ref "U3") (pin "4") (pinfunction "4_4") (pintype "passive"))
      (node (ref "U3") (pin "7") (pinfunction "7_7") (pintype "passive"))
      (node (ref "U3") (pin "8") (pinfunction "8_8") (pintype "passive"))
      (node (ref "U6") (pin "3") (pinfunction "3_3") (pintype "passive"))
      (node (ref "U6") (pin "4") (pinfunction "4_4") (pintype "passive"))
      (node (ref "U6") (pin "7") (pinfunction "7_7") (pintype "passive"))
      (node (ref "U6") (pin "8") (pinfunction "8_8") (pintype "passive"))
    )
    (net (code "55") (name "VIN") (class "Default")
      (node (ref "R34") (pin "2") (pinfunction "2_2") (pintype "passive"))
      (node (ref "U6") (pin "1") (pinfunction "1_1") (pintype "passive"))
      (node (ref "U6") (pin "2") (pinfunction "2_2") (pintype "passive"))
    )
    (net (code "56") (name "unconnected-(LED6-DOU-Pad2)") (class "Default")
      (node (ref "LED6") (pin "2") (pinfunction "DOU_2") (pintype "passive+no_connect"))
    )
    (net (code "57") (name "unconnected-(U2-VREF-Pad5)") (class "Default")
      (node (ref "U2") (pin "5") (pinfunction "VREF_5") (pintype "passive+no_connect"))
    )
    (net (code "58") (name "unconnected-(U4-PA6-Pad14)") (class "Default")
      (node (ref "U4") (pin "14") (pinfunction "PA6_14") (pintype "passive"))
    )
    (net (code "59") (name "unconnected-(U4-PB3-Pad40)") (class "Default")
      (node (ref "U4") (pin "40") (pinfunction "PB3_40") (pintype "passive"))
    )
    (net (code "60") (name "unconnected-(U4-PB6-Pad43)") (class "Default")
      (node (ref "U4") (pin "43") (pinfunction "PB6_43") (pintype "passive"))
    )
    (net (code "61") (name "unconnected-(U4-PB7-Pad44)") (class "Default")
      (node (ref "U4") (pin "44") (pinfunction "PB7_44") (pintype "passive"))
    )
    (net (code "62") (name "unconnected-(U4-PB10-Pad22)") (class "Default")
      (node (ref "U4") (pin "22") (pinfunction "PB10_22") (pintype "passive"))
    )
    (net (code "63") (name "unconnected-(U4-PB14-Pad28)") (class "Default")
      (node (ref "U4") (pin "28") (pinfunction "PB14_28") (pintype "passive"))
    )
    (net (code "64") (name "unconnected-(U4-PB15-Pad29)") (class "Default")
      (node (ref "U4") (pin "29") (pinfunction "PB15_29") (pintype "passive"))
    )
    (net (code "65") (name "unconnected-(U4-PC13-Pad2)") (class "Default")
      (node (ref "U4") (pin "2") (pinfunction "PC13_2") (pintype "passive"))
    )
    (net (code "66") (name "unconnected-(U4-PC14-Pad3)") (class "Default")
      (node (ref "U4") (pin "3") (pinfunction "PC14_3") (pintype "passive"))
    )
    (net (code "67") (name "unconnected-(U4-PC15-Pad4)") (class "Default")
      (node (ref "U4") (pin "4") (pinfunction "PC15_4") (pintype "passive"))
    )
    (net (code "68") (name "unconnected-(U5-VREF-Pad5)") (class "Default")
      (node (ref "U5") (pin "5") (pinfunction "VREF_5") (pintype "passive+no_connect"))
    )
    (net (code "69") (name "unconnected-(U8-VREF-Pad5)") (class "Default")
      (node (ref "U8") (pin "5") (pinfunction "VREF_5") (pintype "passive+no_connect"))
    )
    (net (code "70") (name "unconnected-(U9-Pad3)") (class "Default")
      (node (ref "U9") (pin "3") (pinfunction "3_3") (pintype "passive"))
    )
    (net (code "71") (name "unconnected-(U9-Pad6)") (class "Default")
      (node (ref "U9") (pin "6") (pinfunction "6_6") (pintype "passive+no_connect"))
    )
    (net (code "72") (name "unconnected-(U10-Pad3)") (class "Default")
      (node (ref "U10") (pin "3") (pinfunction "3_3") (pintype "passive"))
    )
    (net (code "73") (name "unconnected-(U10-Pad6)") (class "Default")
      (node (ref "U10") (pin "6") (pinfunction "6_6") (pintype "passive+no_connect"))
    )
    (net (code "74") (name "unconnected-(U11-Pad3)") (class "Default")
      (node (ref "U11") (pin "3") (pinfunction "3_3") (pintype "passive"))
    )
    (net (code "75") (name "unconnected-(U11-Pad6)") (class "Default")
      (node (ref "U11") (pin "6") (pinfunction "6_6") (pintype "passive+no_connect"))
    )
    (net (code "76") (name "unconnected-(U12-Pad3)") (class "Default")
      (node (ref "U12") (pin "3") (pinfunction "3_3") (pintype "passive"))
    )
    (net (code "77") (name "unconnected-(U12-Pad6)") (class "Default")
      (node (ref "U12") (pin "6") (pinfunction "6_6") (pintype "passive+no_connect"))
    )
    (net (code "78") (name "unconnected-(USB1-SBU1-Pad9)") (class "Default")
      (node (ref "USB1") (pin "9") (pinfunction "SBU1_9") (pintype "passive+no_connect"))
    )
    (net (code "79") (name "unconnected-(USB1-SBU2-Pad3)") (class "Default")
      (node (ref "USB1") (pin "3") (pinfunction "SBU2_3") (pintype "passive+no_connect"))
    )
    (net (code "80") (name "unconnected-(USB1-VBUS-Pad2)") (class "Default")
      (node (ref "USB1") (pin "2") (pinfunction "VBUS_2") (pintype "passive+no_connect"))
    )
    (net (code "81") (name "unconnected-(USB1-VBUS-Pad11)") (class "Default")
      (node (ref "USB1") (pin "11") (pinfunction "VBUS_11") (pintype "passive+no_connect"))
    )
  )
)
